# OCTA-STM.net
KiCad netlist of a schematic drawn in EAGLE
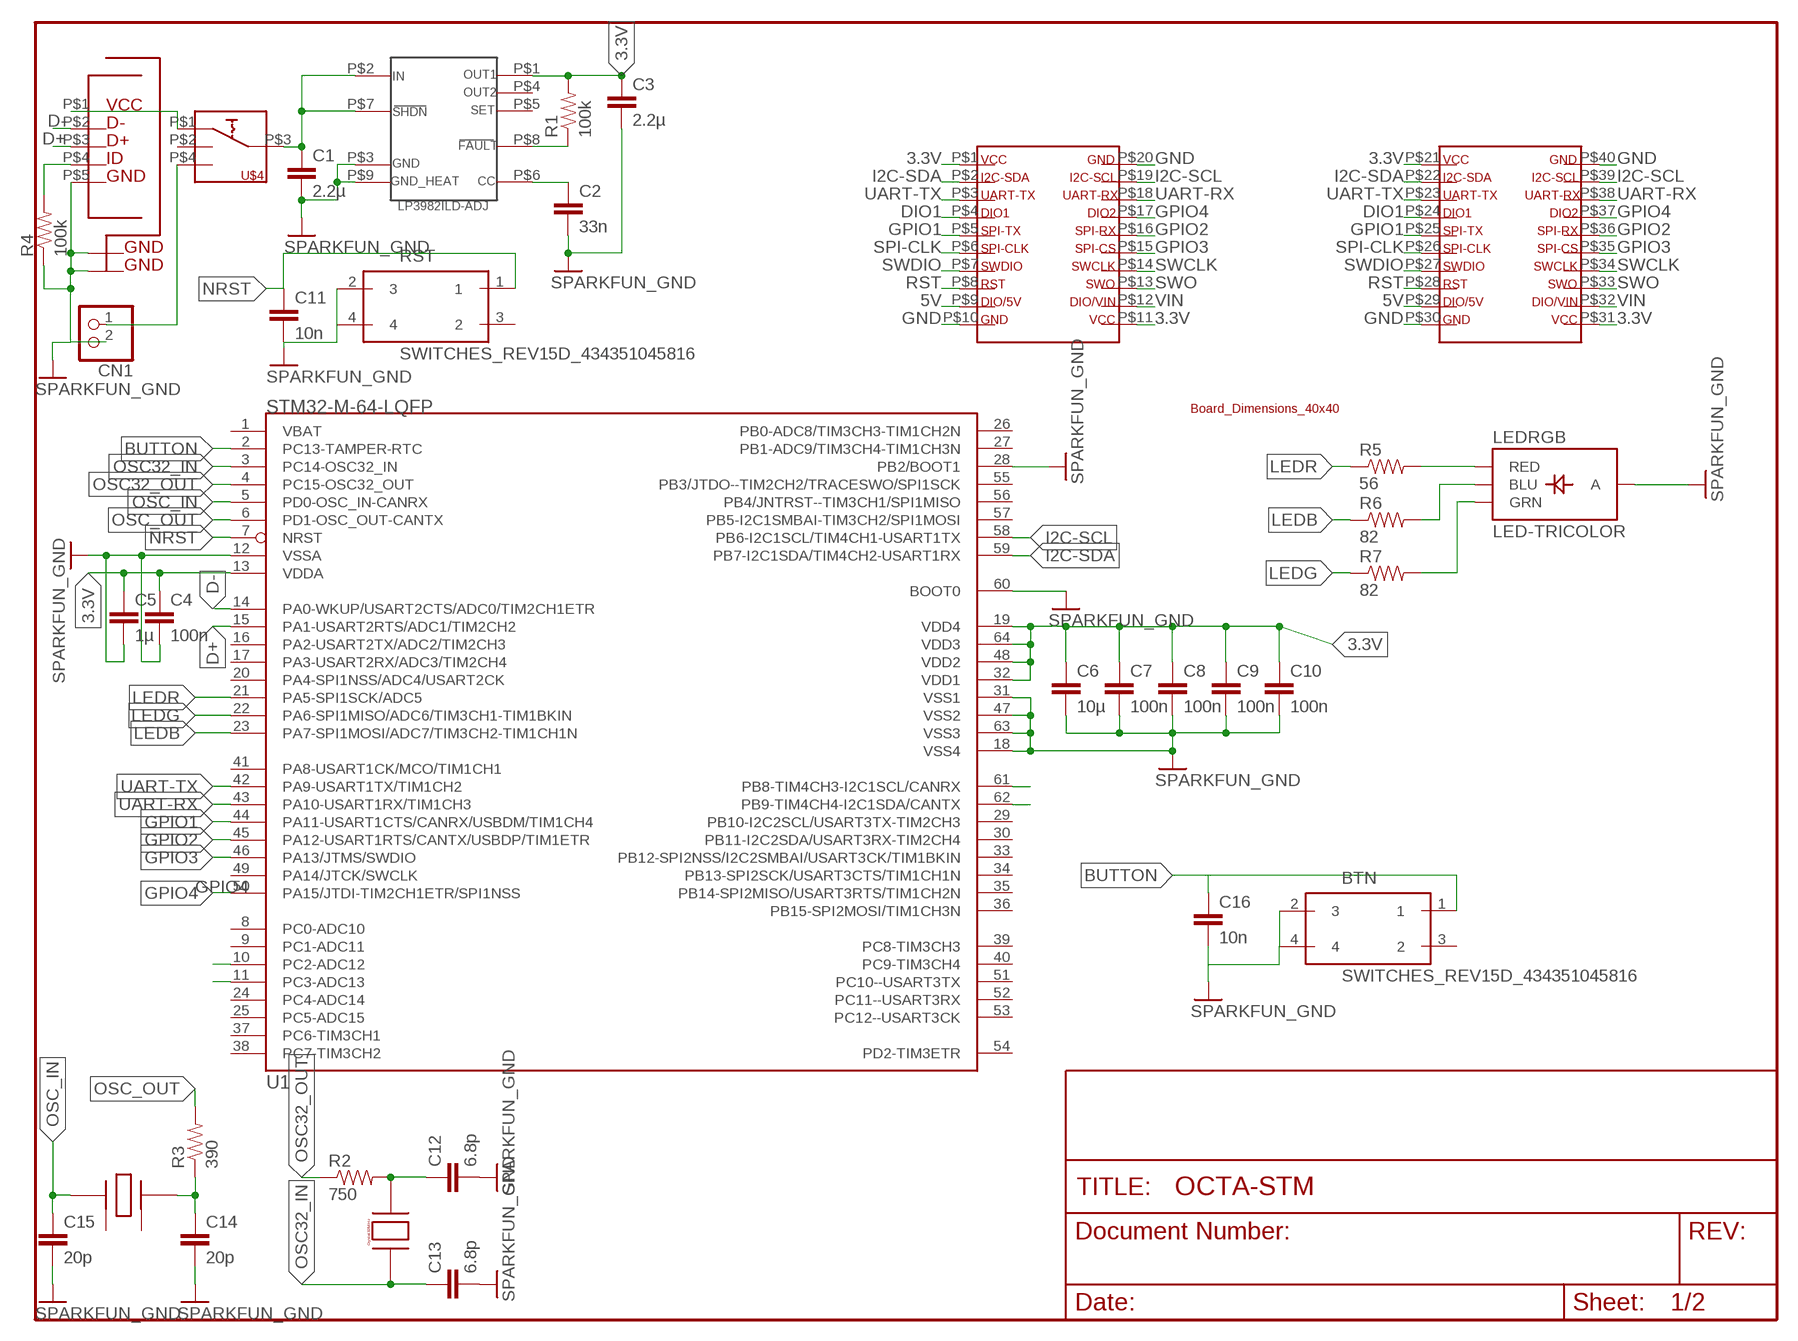
[diagram p0: schematic, sheet 1]
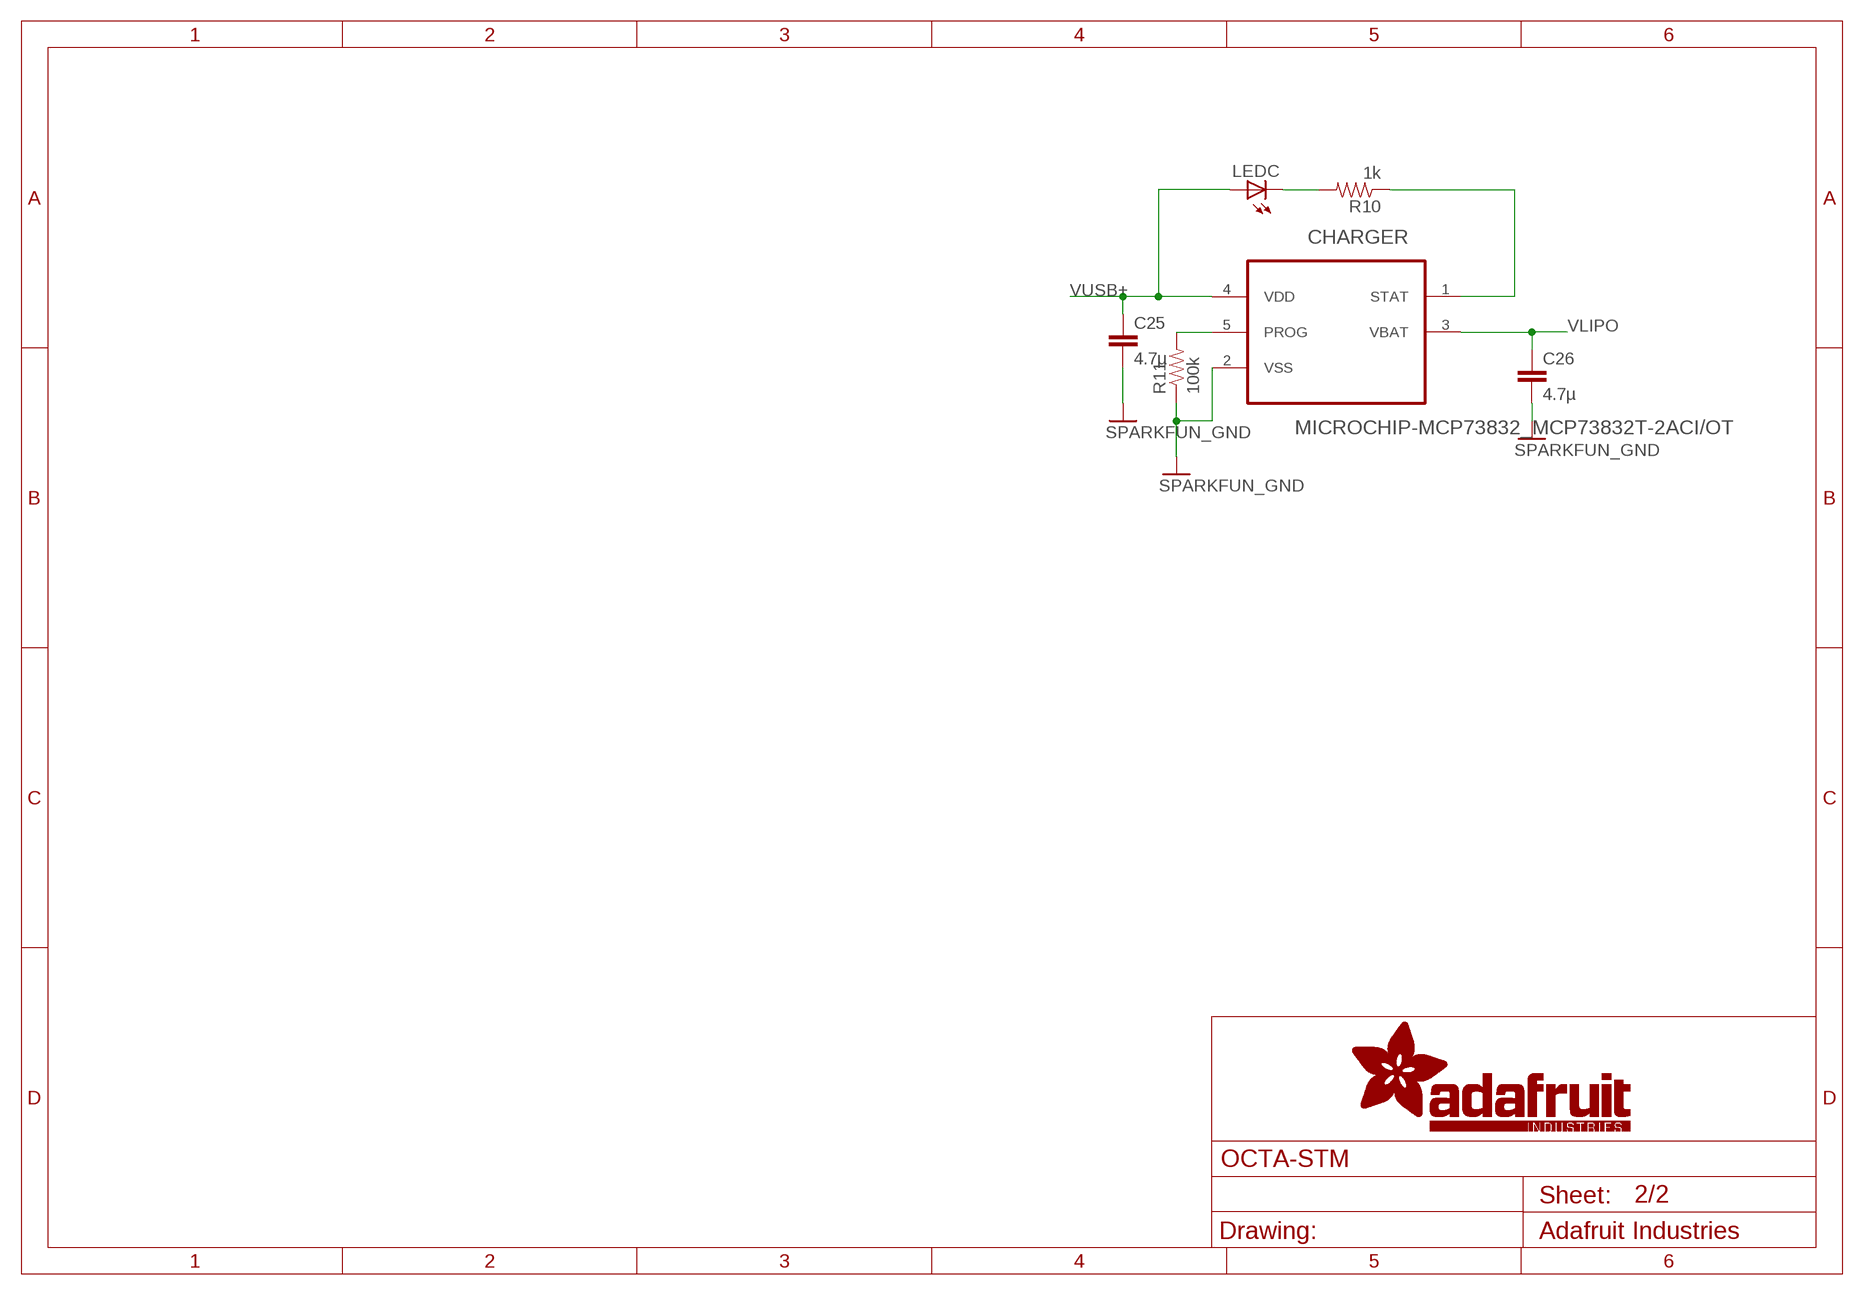
[diagram p1: schematic, sheet 2]

(export (version "E")
  (design (tool "Eeschema 10.0.6"))
  (components
    (comp (ref "BTN")
      (value "SWITCHES_REV15D_434351045816")
      (footprint "eagle-import:SWITCHES_REV15D_434351045816")
      (libsource (lib "eagle-import") (part "SWITCHES_REV15D_434351045816"))
    )
    (comp (ref "C1")
      (value "2.2µ")
      (footprint "eagle-import:SPARKFUN_0603-CAP")
      (libsource (lib "eagle-import") (part "SPARKFUN_CAP0603-CAP"))
    )
    (comp (ref "C2")
      (value "33n")
      (footprint "eagle-import:SPARKFUN_0603-CAP")
      (libsource (lib "eagle-import") (part "SPARKFUN_CAP0603-CAP"))
    )
    (comp (ref "C3")
      (value "2.2µ")
      (footprint "eagle-import:SPARKFUN_0603-CAP")
      (libsource (lib "eagle-import") (part "SPARKFUN_CAP0603-CAP"))
    )
    (comp (ref "C4")
      (value "100n")
      (footprint "eagle-import:SPARKFUN_0603-CAP")
      (libsource (lib "eagle-import") (part "SPARKFUN_CAP0603-CAP"))
    )
    (comp (ref "C5")
      (value "1µ")
      (footprint "eagle-import:SPARKFUN_0603-CAP")
      (libsource (lib "eagle-import") (part "SPARKFUN_CAP0603-CAP"))
    )
    (comp (ref "C6")
      (value "10µ")
      (footprint "eagle-import:SPARKFUN_0603-CAP")
      (libsource (lib "eagle-import") (part "SPARKFUN_CAP0603-CAP"))
    )
    (comp (ref "C7")
      (value "100n")
      (footprint "eagle-import:SPARKFUN_0603-CAP")
      (libsource (lib "eagle-import") (part "SPARKFUN_CAP0603-CAP"))
    )
    (comp (ref "C8")
      (value "100n")
      (footprint "eagle-import:SPARKFUN_0603-CAP")
      (libsource (lib "eagle-import") (part "SPARKFUN_CAP0603-CAP"))
    )
    (comp (ref "C9")
      (value "100n")
      (footprint "eagle-import:SPARKFUN_0603-CAP")
      (libsource (lib "eagle-import") (part "SPARKFUN_CAP0603-CAP"))
    )
    (comp (ref "C10")
      (value "100n")
      (footprint "eagle-import:SPARKFUN_0603-CAP")
      (libsource (lib "eagle-import") (part "SPARKFUN_CAP0603-CAP"))
    )
    (comp (ref "C11")
      (value "10n")
      (footprint "eagle-import:SPARKFUN_0603-CAP")
      (libsource (lib "eagle-import") (part "SPARKFUN_CAP0603-CAP"))
    )
    (comp (ref "C12")
      (value "6.8p")
      (footprint "eagle-import:SPARKFUN_0603-CAP")
      (libsource (lib "eagle-import") (part "SPARKFUN_CAP0603-CAP"))
    )
    (comp (ref "C13")
      (value "6.8p")
      (footprint "eagle-import:SPARKFUN_0603-CAP")
      (libsource (lib "eagle-import") (part "SPARKFUN_CAP0603-CAP"))
    )
    (comp (ref "C14")
      (value "20p")
      (footprint "eagle-import:SPARKFUN_0603-CAP")
      (libsource (lib "eagle-import") (part "SPARKFUN_CAP0603-CAP"))
    )
    (comp (ref "C15")
      (value "20p")
      (footprint "eagle-import:SPARKFUN_0603-CAP")
      (libsource (lib "eagle-import") (part "SPARKFUN_CAP0603-CAP"))
    )
    (comp (ref "C16")
      (value "10n")
      (footprint "eagle-import:SPARKFUN_0603-CAP")
      (libsource (lib "eagle-import") (part "SPARKFUN_CAP0603-CAP"))
    )
    (comp (ref "CN1")
      (value "ADAFRUIT_JST_2PIN-SMT-RA")
      (footprint "eagle-import:ADAFRUIT_JST-PH-2-SMT-RA")
      (libsource (lib "eagle-import") (part "ADAFRUIT_JST_2PIN-SMT-RA"))
    )
    (comp (ref "LEDRGB")
      (value "LED-TRICOLOR")
      (footprint "eagle-import:LED-TRICOLOR-SMD")
      (libsource (lib "eagle-import") (part "LED-TRICOLOR"))
    )
    (comp (ref "R1")
      (value "100k")
      (footprint "eagle-import:SPARKFUN_0603-RES")
      (libsource (lib "eagle-import") (part "SPARKFUN_RESISTOR0603-RES"))
    )
    (comp (ref "R2")
      (value "750")
      (footprint "eagle-import:SPARKFUN_0603-RES")
      (libsource (lib "eagle-import") (part "SPARKFUN_RESISTOR0603-RES"))
    )
    (comp (ref "R3")
      (value "390")
      (footprint "eagle-import:SPARKFUN_0603-RES")
      (libsource (lib "eagle-import") (part "SPARKFUN_RESISTOR0603-RES"))
    )
    (comp (ref "R4")
      (value "100k")
      (footprint "eagle-import:SPARKFUN_0603-RES")
      (libsource (lib "eagle-import") (part "SPARKFUN_RESISTOR0603-RES"))
    )
    (comp (ref "R5")
      (value "56")
      (footprint "eagle-import:SPARKFUN_0603-RES")
      (libsource (lib "eagle-import") (part "SPARKFUN_RESISTOR0603-RES"))
    )
    (comp (ref "R6")
      (value "82")
      (footprint "eagle-import:SPARKFUN_0603-RES")
      (libsource (lib "eagle-import") (part "SPARKFUN_RESISTOR0603-RES"))
    )
    (comp (ref "R7")
      (value "82")
      (footprint "eagle-import:SPARKFUN_0603-RES")
      (libsource (lib "eagle-import") (part "SPARKFUN_RESISTOR0603-RES"))
    )
    (comp (ref "RST")
      (value "SWITCHES_REV15D_434351045816")
      (footprint "eagle-import:SWITCHES_REV15D_434351045816")
      (libsource (lib "eagle-import") (part "SWITCHES_REV15D_434351045816"))
    )
    (comp (ref "U$1")
      (value "OCTA-CORE_MCIRO-USB2")
      (footprint "eagle-import:OCTA-CORE_MICRO-USB2")
      (libsource (lib "eagle-import") (part "OCTA-CORE_MCIRO-USB2"))
    )
    (comp (ref "U$2")
      (value "BOARD-DIMENSIONS-40X40")
      (footprint "eagle-import:BOARD-DIMENSIONS-40X40")
      (libsource (lib "eagle-import") (part "BOARD-DIMENSIONS-40X40"))
    )
    (comp (ref "U$3")
      (value "DRAGAN-PERSONAL_TI-3.3V-REGULATOR")
      (footprint "eagle-import:DRAGAN-PERSONAL_TI-3.3V-REGULATOR")
      (libsource (lib "eagle-import") (part "DRAGAN-PERSONAL_TI-3.3V-REGULATOR"))
    )
    (comp (ref "U$4")
      (value "OCTA-CORE_SP3T")
      (footprint "eagle-import:OCTA-CORE_SP3T")
      (libsource (lib "eagle-import") (part "OCTA-CORE_SP3T"))
    )
    (comp (ref "U$5")
      (value "DRAGAN-PERSONAL_CRYSTAL_32MHZ")
      (footprint "eagle-import:DRAGAN-PERSONAL_CRYSTAL_32MHZ")
      (libsource (lib "eagle-import") (part "DRAGAN-PERSONAL_CRYSTAL_32MHZ"))
    )
    (comp (ref "U$7")
      (value "DRAGAN-PERSONAL_XTAL-26MHZ")
      (footprint "eagle-import:DRAGAN-PERSONAL_XTAL-26MHZ")
      (libsource (lib "eagle-import") (part "DRAGAN-PERSONAL_XTAL-26MHZ"))
    )
    (comp (ref "U1")
      (value "STM32-M-64-LQFP")
      (footprint "eagle-import:LQFP64")
      (libsource (lib "eagle-import") (part "STM32-M-64-LQFP"))
    )
    (comp (ref "C25")
      (value "4.7µ")
      (footprint "eagle-import:SPARKFUN_0603-CAP")
      (libsource (lib "eagle-import") (part "SPARKFUN_CAP0603-CAP"))
    )
    (comp (ref "C26")
      (value "4.7µ")
      (footprint "eagle-import:SPARKFUN_0603-CAP")
      (libsource (lib "eagle-import") (part "SPARKFUN_CAP0603-CAP"))
    )
    (comp (ref "CHARGER")
      (value "MICROCHIP-MCP73832_MCP73832T-2ACI/OT")
      (footprint "eagle-import:MICROCHIP-MCP73832_SOT95P280X145-5N")
      (fields (field (name "MPN") "MCP73832T-2ACI/OT"))
      (libsource (lib "eagle-import") (part "MICROCHIP-MCP73832_MCP73832T-2ACI/OT"))
    )
    (comp (ref "LEDC")
      (value "LED_LEDCHIP-LED0805")
      (footprint "eagle-import:LED_CHIP-LED0805")
      (libsource (lib "eagle-import") (part "LED_LEDCHIP-LED0805"))
    )
    (comp (ref "R10")
      (value "1k")
      (footprint "eagle-import:SPARKFUN_0603-RES")
      (libsource (lib "eagle-import") (part "SPARKFUN_RESISTOR0603-RES"))
    )
    (comp (ref "R11")
      (value "100k")
      (footprint "eagle-import:SPARKFUN_0603-RES")
      (libsource (lib "eagle-import") (part "SPARKFUN_RESISTOR0603-RES"))
    )
  )
  (nets
    (net (code "1") (name "3.3V") (class "Default")
      (node (ref "C10") (pin "1") (pinfunction "1_1") (pintype "passive"))
      (node (ref "C3") (pin "1") (pinfunction "1_1") (pintype "passive"))
      (node (ref "C4") (pin "1") (pinfunction "1_1") (pintype "passive"))
      (node (ref "C5") (pin "1") (pinfunction "1_1") (pintype "passive"))
      (node (ref "C6") (pin "1") (pinfunction "1_1") (pintype "passive"))
      (node (ref "C7") (pin "1") (pinfunction "1_1") (pintype "passive"))
      (node (ref "C8") (pin "1") (pinfunction "1_1") (pintype "passive"))
      (node (ref "C9") (pin "1") (pinfunction "1_1") (pintype "passive"))
      (node (ref "R1") (pin "2") (pinfunction "2_2") (pintype "passive"))
      (node (ref "U$2") (pin "P$1") (pinfunction "P$1_P$1") (pintype "bidirectional"))
      (node (ref "U$2") (pin "P$11") (pinfunction "P$11_P$11") (pintype "bidirectional"))
      (node (ref "U$2") (pin "P$21") (pinfunction "P$21_P$21") (pintype "bidirectional"))
      (node (ref "U$2") (pin "P$31") (pinfunction "P$31_P$31") (pintype "bidirectional"))
      (node (ref "U$3") (pin "P$1") (pinfunction "P$1_P$1") (pintype "bidirectional"))
      (node (ref "U1") (pin "13") (pinfunction "VDDA_13") (pintype "power_in"))
      (node (ref "U1") (pin "19") (pinfunction "VDD4_19") (pintype "bidirectional"))
      (node (ref "U1") (pin "32") (pinfunction "VDD1_32") (pintype "power_in"))
      (node (ref "U1") (pin "48") (pinfunction "VDD2_48") (pintype "power_in"))
      (node (ref "U1") (pin "64") (pinfunction "VDD3_64") (pintype "power_in"))
    )
    (net (code "2") (name "5V") (class "Default")
      (node (ref "U$2") (pin "P$29") (pinfunction "P$29_P$29") (pintype "bidirectional"))
      (node (ref "U$2") (pin "P$9") (pinfunction "P$9_P$9") (pintype "bidirectional"))
    )
    (net (code "3") (name "BUTTON") (class "Default")
      (node (ref "BTN") (pin "1") (pinfunction "1_1") (pintype "bidirectional"))
      (node (ref "C16") (pin "1") (pinfunction "1_1") (pintype "passive"))
      (node (ref "U1") (pin "2") (pinfunction "PC13-TAMPER-RTC_2") (pintype "bidirectional"))
    )
    (net (code "4") (name "D+") (class "Default")
      (node (ref "U$1") (pin "P$3") (pinfunction "P$3_P$3") (pintype "bidirectional"))
      (node (ref "U1") (pin "15") (pinfunction "PA1-USART2RTS/ADC1/TIM2CH2_15") (pintype "bidirectional"))
    )
    (net (code "5") (name "D-") (class "Default")
      (node (ref "U$1") (pin "P$2") (pinfunction "P$2_P$2") (pintype "bidirectional"))
      (node (ref "U1") (pin "14") (pinfunction "PA0-WKUP/USART2CTS/ADC0/TIM2CH1ETR_14") (pintype "bidirectional"))
    )
    (net (code "6") (name "DIO1") (class "Default")
      (node (ref "U$2") (pin "P$24") (pinfunction "P$24_P$24") (pintype "bidirectional"))
      (node (ref "U$2") (pin "P$4") (pinfunction "P$4_P$4") (pintype "bidirectional"))
    )
    (net (code "7") (name "GND") (class "Default")
      (node (ref "BTN") (pin "2") (pinfunction "3_2") (pintype "bidirectional"))
      (node (ref "BTN") (pin "4") (pinfunction "4_4") (pintype "bidirectional"))
      (node (ref "C1") (pin "2") (pinfunction "2_2") (pintype "passive"))
      (node (ref "C10") (pin "2") (pinfunction "2_2") (pintype "passive"))
      (node (ref "C11") (pin "2") (pinfunction "2_2") (pintype "passive"))
      (node (ref "C12") (pin "2") (pinfunction "2_2") (pintype "passive"))
      (node (ref "C13") (pin "2") (pinfunction "2_2") (pintype "passive"))
      (node (ref "C14") (pin "2") (pinfunction "2_2") (pintype "passive"))
      (node (ref "C15") (pin "2") (pinfunction "2_2") (pintype "passive"))
      (node (ref "C16") (pin "2") (pinfunction "2_2") (pintype "passive"))
      (node (ref "C2") (pin "2") (pinfunction "2_2") (pintype "passive"))
      (node (ref "C25") (pin "2") (pinfunction "2_2") (pintype "passive"))
      (node (ref "C26") (pin "2") (pinfunction "2_2") (pintype "passive"))
      (node (ref "C3") (pin "2") (pinfunction "2_2") (pintype "passive"))
      (node (ref "C4") (pin "2") (pinfunction "2_2") (pintype "passive"))
      (node (ref "C5") (pin "2") (pinfunction "2_2") (pintype "passive"))
      (node (ref "C6") (pin "2") (pinfunction "2_2") (pintype "passive"))
      (node (ref "C7") (pin "2") (pinfunction "2_2") (pintype "passive"))
      (node (ref "C8") (pin "2") (pinfunction "2_2") (pintype "passive"))
      (node (ref "C9") (pin "2") (pinfunction "2_2") (pintype "passive"))
      (node (ref "CHARGER") (pin "2") (pinfunction "VSS_2") (pintype "power_in"))
      (node (ref "CN1") (pin "2") (pinfunction "1_2") (pintype "passive"))
      (node (ref "LEDRGB") (pin "A") (pinfunction "A_A") (pintype "bidirectional"))
      (node (ref "R11") (pin "1") (pinfunction "1_1") (pintype "passive"))
      (node (ref "R4") (pin "1") (pinfunction "1_1") (pintype "passive"))
      (node (ref "RST") (pin "2") (pinfunction "3_2") (pintype "bidirectional"))
      (node (ref "RST") (pin "4") (pinfunction "4_4") (pintype "bidirectional"))
      (node (ref "U$1") (pin "P$10") (pinfunction "P$7_P$10") (pintype "bidirectional"))
      (node (ref "U$1") (pin "P$11") (pinfunction "P$7_P$11") (pintype "bidirectional"))
      (node (ref "U$1") (pin "P$12") (pinfunction "P$6_P$12") (pintype "bidirectional"))
      (node (ref "U$1") (pin "P$13") (pinfunction "P$6_P$13") (pintype "bidirectional"))
      (node (ref "U$1") (pin "P$5") (pinfunction "P$5_P$5") (pintype "bidirectional"))
      (node (ref "U$1") (pin "P$6") (pinfunction "P$6_P$6") (pintype "bidirectional"))
      (node (ref "U$1") (pin "P$7") (pinfunction "P$6_P$7") (pintype "bidirectional"))
      (node (ref "U$1") (pin "P$8") (pinfunction "P$7_P$8") (pintype "bidirectional"))
      (node (ref "U$1") (pin "P$9") (pinfunction "P$7_P$9") (pintype "bidirectional"))
      (node (ref "U$2") (pin "P$10") (pinfunction "P$10_P$10") (pintype "bidirectional"))
      (node (ref "U$2") (pin "P$20") (pinfunction "P$20_P$20") (pintype "bidirectional"))
      (node (ref "U$2") (pin "P$30") (pinfunction "P$30_P$30") (pintype "bidirectional"))
      (node (ref "U$2") (pin "P$40") (pinfunction "P$40_P$40") (pintype "bidirectional"))
      (node (ref "U$3") (pin "P$3") (pinfunction "P$3_P$3") (pintype "bidirectional"))
      (node (ref "U$3") (pin "P$9") (pinfunction "P$9_P$9") (pintype "bidirectional"))
      (node (ref "U1") (pin "12") (pinfunction "VSSA_12") (pintype "power_in"))
      (node (ref "U1") (pin "18") (pinfunction "VSS4_18") (pintype "bidirectional"))
      (node (ref "U1") (pin "28") (pinfunction "PB2/BOOT1_28") (pintype "bidirectional"))
      (node (ref "U1") (pin "31") (pinfunction "VSS1_31") (pintype "power_in"))
      (node (ref "U1") (pin "47") (pinfunction "VSS2_47") (pintype "power_in"))
      (node (ref "U1") (pin "60") (pinfunction "BOOT0_60") (pintype "input"))
      (node (ref "U1") (pin "63") (pinfunction "VSS3_63") (pintype "power_in"))
    )
    (net (code "8") (name "GPIO1") (class "Default")
      (node (ref "U$2") (pin "P$25") (pinfunction "P$25_P$25") (pintype "bidirectional"))
      (node (ref "U$2") (pin "P$5") (pinfunction "P$5_P$5") (pintype "bidirectional"))
      (node (ref "U1") (pin "44") (pinfunction "PA11-USART1CTS/CANRX/USBDM/TIM1CH4_44") (pintype "bidirectional"))
    )
    (net (code "9") (name "GPIO2") (class "Default")
      (node (ref "U$2") (pin "P$16") (pinfunction "P$16_P$16") (pintype "bidirectional"))
      (node (ref "U$2") (pin "P$36") (pinfunction "P$36_P$36") (pintype "bidirectional"))
      (node (ref "U1") (pin "45") (pinfunction "PA12-USART1RTS/CANTX/USBDP/TIM1ETR_45") (pintype "bidirectional"))
    )
    (net (code "10") (name "GPIO3") (class "Default")
      (node (ref "U$2") (pin "P$15") (pinfunction "P$15_P$15") (pintype "bidirectional"))
      (node (ref "U$2") (pin "P$35") (pinfunction "P$35_P$35") (pintype "bidirectional"))
      (node (ref "U1") (pin "46") (pinfunction "PA13/JTMS/SWDIO_46") (pintype "bidirectional"))
    )
    (net (code "11") (name "GPIO4") (class "Default")
      (node (ref "U$2") (pin "P$17") (pinfunction "P$17_P$17") (pintype "bidirectional"))
      (node (ref "U$2") (pin "P$37") (pinfunction "P$37_P$37") (pintype "bidirectional"))
      (node (ref "U1") (pin "50") (pinfunction "PA15/JTDI-TIM2CH1ETR/SPI1NSS_50") (pintype "bidirectional"))
    )
    (net (code "12") (name "I2C-SCL") (class "Default")
      (node (ref "U$2") (pin "P$19") (pinfunction "P$19_P$19") (pintype "bidirectional"))
      (node (ref "U$2") (pin "P$39") (pinfunction "P$39_P$39") (pintype "bidirectional"))
      (node (ref "U1") (pin "58") (pinfunction "PB6-I2C1SCL/TIM4CH1-USART1TX_58") (pintype "bidirectional"))
    )
    (net (code "13") (name "I2C-SDA") (class "Default")
      (node (ref "U$2") (pin "P$2") (pinfunction "P$2_P$2") (pintype "bidirectional"))
      (node (ref "U$2") (pin "P$22") (pinfunction "P$22_P$22") (pintype "bidirectional"))
      (node (ref "U1") (pin "59") (pinfunction "PB7-I2C1SDA/TIM4CH2-USART1RX_59") (pintype "bidirectional"))
    )
    (net (code "14") (name "LEDB") (class "Default")
      (node (ref "R6") (pin "1") (pinfunction "1_1") (pintype "passive"))
      (node (ref "U1") (pin "23") (pinfunction "PA7-SPI1MOSI/ADC7/TIM3CH2-TIM1CH1N_23") (pintype "bidirectional"))
    )
    (net (code "15") (name "LEDG") (class "Default")
      (node (ref "R7") (pin "1") (pinfunction "1_1") (pintype "passive"))
      (node (ref "U1") (pin "22") (pinfunction "PA6-SPI1MISO/ADC6/TIM3CH1-TIM1BKIN_22") (pintype "bidirectional"))
    )
    (net (code "16") (name "LEDR") (class "Default")
      (node (ref "R5") (pin "1") (pinfunction "1_1") (pintype "passive"))
      (node (ref "U1") (pin "21") (pinfunction "PA5-SPI1SCK/ADC5_21") (pintype "bidirectional"))
    )
    (net (code "17") (name "NRST") (class "Default")
      (node (ref "C11") (pin "1") (pinfunction "1_1") (pintype "passive"))
      (node (ref "RST") (pin "1") (pinfunction "1_1") (pintype "bidirectional"))
      (node (ref "U1") (pin "7") (pinfunction "NRST_7") (pintype "bidirectional"))
    )
    (net (code "18") (name "Net-(C1-Pad1)") (class "Default")
      (node (ref "C1") (pin "1") (pinfunction "1_1") (pintype "passive"))
      (node (ref "U$3") (pin "P$2") (pinfunction "P$2_P$2") (pintype "bidirectional"))
      (node (ref "U$3") (pin "P$7") (pinfunction "P$7_P$7") (pintype "bidirectional"))
      (node (ref "U$4") (pin "P$3") (pinfunction "P$3_P$3") (pintype "bidirectional"))
    )
    (net (code "19") (name "Net-(C2-Pad1)") (class "Default")
      (node (ref "C2") (pin "1") (pinfunction "1_1") (pintype "passive"))
      (node (ref "U$3") (pin "P$6") (pinfunction "P$6_P$6") (pintype "bidirectional"))
    )
    (net (code "20") (name "Net-(C14-Pad1)") (class "Default")
      (node (ref "C14") (pin "1") (pinfunction "1_1") (pintype "passive"))
      (node (ref "R3") (pin "1") (pinfunction "1_1") (pintype "passive"))
      (node (ref "U$7") (pin "P$3") (pinfunction "P$3_P$3") (pintype "bidirectional"))
    )
    (net (code "21") (name "Net-(CHARGER-PROG)") (class "Default")
      (node (ref "CHARGER") (pin "5") (pinfunction "PROG_5") (pintype "input"))
      (node (ref "R11") (pin "2") (pinfunction "2_2") (pintype "passive"))
    )
    (net (code "22") (name "Net-(CHARGER-STAT)") (class "Default")
      (node (ref "CHARGER") (pin "1") (pinfunction "STAT_1") (pintype "output"))
      (node (ref "R10") (pin "1") (pinfunction "1_1") (pintype "passive"))
    )
    (net (code "23") (name "Net-(LEDC-PadC)") (class "Default")
      (node (ref "LEDC") (pin "C") (pinfunction "C_C") (pintype "passive"))
      (node (ref "R10") (pin "2") (pinfunction "2_2") (pintype "passive"))
    )
    (net (code "24") (name "Net-(LEDRGB-BLU)") (class "Default")
      (node (ref "LEDRGB") (pin "B") (pinfunction "BLU_B") (pintype "bidirectional"))
      (node (ref "R6") (pin "2") (pinfunction "2_2") (pintype "passive"))
    )
    (net (code "25") (name "Net-(LEDRGB-GRN)") (class "Default")
      (node (ref "LEDRGB") (pin "G") (pinfunction "GRN_G") (pintype "bidirectional"))
      (node (ref "R7") (pin "2") (pinfunction "2_2") (pintype "passive"))
    )
    (net (code "26") (name "Net-(LEDRGB-RED)") (class "Default")
      (node (ref "LEDRGB") (pin "R") (pinfunction "RED_R") (pintype "bidirectional"))
      (node (ref "R5") (pin "2") (pinfunction "2_2") (pintype "passive"))
    )
    (net (code "27") (name "Net-(R1-Pad1)") (class "Default")
      (node (ref "R1") (pin "1") (pinfunction "1_1") (pintype "passive"))
      (node (ref "U$3") (pin "P$8") (pinfunction "P$8_P$8") (pintype "bidirectional"))
    )
    (net (code "28") (name "Net-(R4-Pad2)") (class "Default")
      (node (ref "R4") (pin "2") (pinfunction "2_2") (pintype "passive"))
      (node (ref "U$1") (pin "P$4") (pinfunction "P$4_P$4") (pintype "bidirectional"))
    )
    (net (code "29") (name "Net-(U$5-P$1)") (class "Default")
      (node (ref "C12") (pin "1") (pinfunction "1_1") (pintype "passive"))
      (node (ref "R2") (pin "2") (pinfunction "2_2") (pintype "passive"))
      (node (ref "U$5") (pin "P$2") (pinfunction "P$1_P$2") (pintype "bidirectional"))
    )
    (net (code "30") (name "OSC32_IN") (class "Default")
      (node (ref "C13") (pin "1") (pinfunction "1_1") (pintype "passive"))
      (node (ref "U$5") (pin "P$3") (pinfunction "P$2_P$3") (pintype "bidirectional"))
      (node (ref "U1") (pin "3") (pinfunction "PC14-OSC32_IN_3") (pintype "bidirectional"))
    )
    (net (code "31") (name "OSC32_OUT") (class "Default")
      (node (ref "R2") (pin "1") (pinfunction "1_1") (pintype "passive"))
      (node (ref "U1") (pin "4") (pinfunction "PC15-OSC32_OUT_4") (pintype "bidirectional"))
    )
    (net (code "32") (name "OSC_IN") (class "Default")
      (node (ref "C15") (pin "1") (pinfunction "1_1") (pintype "passive"))
      (node (ref "U$7") (pin "P$1") (pinfunction "P$1_P$1") (pintype "bidirectional"))
      (node (ref "U1") (pin "5") (pinfunction "PD0-OSC_IN-CANRX_5") (pintype "input"))
    )
    (net (code "33") (name "OSC_OUT") (class "Default")
      (node (ref "R3") (pin "2") (pinfunction "2_2") (pintype "passive"))
      (node (ref "U1") (pin "6") (pinfunction "PD1-OSC_OUT-CANTX_6") (pintype "output"))
    )
    (net (code "34") (name "RST") (class "Default")
      (node (ref "U$2") (pin "P$28") (pinfunction "P$28_P$28") (pintype "bidirectional"))
      (node (ref "U$2") (pin "P$8") (pinfunction "P$8_P$8") (pintype "bidirectional"))
    )
    (net (code "35") (name "SPI-CLK") (class "Default")
      (node (ref "U$2") (pin "P$26") (pinfunction "P$26_P$26") (pintype "bidirectional"))
      (node (ref "U$2") (pin "P$6") (pinfunction "P$6_P$6") (pintype "bidirectional"))
    )
    (net (code "36") (name "SWCLK") (class "Default")
      (node (ref "U$2") (pin "P$14") (pinfunction "P$14_P$14") (pintype "bidirectional"))
      (node (ref "U$2") (pin "P$34") (pinfunction "P$34_P$34") (pintype "bidirectional"))
    )
    (net (code "37") (name "SWDIO") (class "Default")
      (node (ref "U$2") (pin "P$27") (pinfunction "P$27_P$27") (pintype "bidirectional"))
      (node (ref "U$2") (pin "P$7") (pinfunction "P$7_P$7") (pintype "bidirectional"))
    )
    (net (code "38") (name "SWO") (class "Default")
      (node (ref "U$2") (pin "P$13") (pinfunction "P$13_P$13") (pintype "bidirectional"))
      (node (ref "U$2") (pin "P$33") (pinfunction "P$33_P$33") (pintype "bidirectional"))
    )
    (net (code "39") (name "UART-RX") (class "Default")
      (node (ref "U$2") (pin "P$18") (pinfunction "P$18_P$18") (pintype "bidirectional"))
      (node (ref "U$2") (pin "P$38") (pinfunction "P$38_P$38") (pintype "bidirectional"))
      (node (ref "U1") (pin "43") (pinfunction "PA10-USART1RX/TIM1CH3_43") (pintype "bidirectional"))
    )
    (net (code "40") (name "UART-TX") (class "Default")
      (node (ref "U$2") (pin "P$23") (pinfunction "P$23_P$23") (pintype "bidirectional"))
      (node (ref "U$2") (pin "P$3") (pinfunction "P$3_P$3") (pintype "bidirectional"))
      (node (ref "U1") (pin "42") (pinfunction "PA9-USART1TX/TIM1CH2_42") (pintype "bidirectional"))
    )
    (net (code "41") (name "VBAT") (class "Default")
      (node (ref "U1") (pin "1") (pinfunction "VBAT_1") (pintype "power_in"))
    )
    (net (code "42") (name "VIN") (class "Default")
      (node (ref "U$2") (pin "P$12") (pinfunction "P$12_P$12") (pintype "bidirectional"))
      (node (ref "U$2") (pin "P$32") (pinfunction "P$32_P$32") (pintype "bidirectional"))
    )
    (net (code "43") (name "VLIPO") (class "Default")
      (node (ref "C26") (pin "1") (pinfunction "1_1") (pintype "passive"))
      (node (ref "CHARGER") (pin "3") (pinfunction "VBAT_3") (pintype "output"))
      (node (ref "CN1") (pin "1") (pinfunction "2_1") (pintype "passive"))
      (node (ref "U$4") (pin "P$4") (pinfunction "P$4_P$4") (pintype "bidirectional"))
    )
    (net (code "44") (name "VUSB+") (class "Default")
      (node (ref "C25") (pin "1") (pinfunction "1_1") (pintype "passive"))
      (node (ref "CHARGER") (pin "4") (pinfunction "VDD_4") (pintype "power_in"))
      (node (ref "LEDC") (pin "A") (pinfunction "A_A") (pintype "passive"))
      (node (ref "U$1") (pin "P$1") (pinfunction "P$1_P$1") (pintype "bidirectional"))
      (node (ref "U$4") (pin "P$1") (pinfunction "P$1_P$1") (pintype "bidirectional"))
    )
    (net (code "45") (name "unconnected-(BTN-2-Pad3)") (class "Default")
      (node (ref "BTN") (pin "3") (pinfunction "2_3") (pintype "bidirectional"))
    )
    (net (code "46") (name "unconnected-(RST-2-Pad3)") (class "Default")
      (node (ref "RST") (pin "3") (pinfunction "2_3") (pintype "bidirectional"))
    )
    (net (code "47") (name "unconnected-(U$3-PadP$4)") (class "Default")
      (node (ref "U$3") (pin "P$4") (pinfunction "P$4_P$4") (pintype "bidirectional"))
    )
    (net (code "48") (name "unconnected-(U$3-PadP$5)") (class "Default")
      (node (ref "U$3") (pin "P$5") (pinfunction "P$5_P$5") (pintype "bidirectional"))
    )
    (net (code "49") (name "unconnected-(U$4-PadP$2)") (class "Default")
      (node (ref "U$4") (pin "P$2") (pinfunction "P$2_P$2") (pintype "bidirectional"))
    )
    (net (code "50") (name "unconnected-(U$7-PadP$2)") (class "Default")
      (node (ref "U$7") (pin "P$2") (pinfunction "P$2_P$2") (pintype "bidirectional"))
    )
    (net (code "51") (name "unconnected-(U$7-PadP$4)") (class "Default")
      (node (ref "U$7") (pin "P$4") (pinfunction "P$4_P$4") (pintype "bidirectional"))
    )
    (net (code "52") (name "unconnected-(U1-PA2-USART2TX{slash}ADC2{slash}TIM2CH3-Pad16)") (class "Default")
      (node (ref "U1") (pin "16") (pinfunction "PA2-USART2TX/ADC2/TIM2CH3_16") (pintype "bidirectional"))
    )
    (net (code "53") (name "unconnected-(U1-PA3-USART2RX{slash}ADC3{slash}TIM2CH4-Pad17)") (class "Default")
      (node (ref "U1") (pin "17") (pinfunction "PA3-USART2RX/ADC3/TIM2CH4_17") (pintype "bidirectional"))
    )
    (net (code "54") (name "unconnected-(U1-PA4-SPI1NSS{slash}ADC4{slash}USART2CK-Pad20)") (class "Default")
      (node (ref "U1") (pin "20") (pinfunction "PA4-SPI1NSS/ADC4/USART2CK_20") (pintype "bidirectional"))
    )
    (net (code "55") (name "unconnected-(U1-PA8-USART1CK{slash}MCO{slash}TIM1CH1-Pad41)") (class "Default")
      (node (ref "U1") (pin "41") (pinfunction "PA8-USART1CK/MCO/TIM1CH1_41") (pintype "bidirectional"))
    )
    (net (code "56") (name "unconnected-(U1-PA14{slash}JTCK{slash}SWCLK-Pad49)") (class "Default")
      (node (ref "U1") (pin "49") (pinfunction "PA14/JTCK/SWCLK_49") (pintype "bidirectional"))
    )
    (net (code "57") (name "unconnected-(U1-PB0-ADC8{slash}TIM3CH3-TIM1CH2N-Pad26)") (class "Default")
      (node (ref "U1") (pin "26") (pinfunction "PB0-ADC8/TIM3CH3-TIM1CH2N_26") (pintype "bidirectional"))
    )
    (net (code "58") (name "unconnected-(U1-PB1-ADC9{slash}TIM3CH4-TIM1CH3N-Pad27)") (class "Default")
      (node (ref "U1") (pin "27") (pinfunction "PB1-ADC9/TIM3CH4-TIM1CH3N_27") (pintype "bidirectional"))
    )
    (net (code "59") (name "unconnected-(U1-PB3{slash}JTDO--TIM2CH2{slash}TRACESWO{slash}SPI1SCK-Pad55)") (class "Default")
      (node (ref "U1") (pin "55") (pinfunction "PB3/JTDO--TIM2CH2/TRACESWO/SPI1SCK_55") (pintype "bidirectional"))
    )
    (net (code "60") (name "unconnected-(U1-PB4{slash}JNTRST--TIM3CH1{slash}SPI1MISO-Pad56)") (class "Default")
      (node (ref "U1") (pin "56") (pinfunction "PB4/JNTRST--TIM3CH1/SPI1MISO_56") (pintype "bidirectional"))
    )
    (net (code "61") (name "unconnected-(U1-PB5-I2C1SMBAI-TIM3CH2{slash}SPI1MOSI-Pad57)") (class "Default")
      (node (ref "U1") (pin "57") (pinfunction "PB5-I2C1SMBAI-TIM3CH2/SPI1MOSI_57") (pintype "bidirectional"))
    )
    (net (code "62") (name "unconnected-(U1-PB8-TIM4CH3-I2C1SCL{slash}CANRX-Pad61)") (class "Default")
      (node (ref "U1") (pin "61") (pinfunction "PB8-TIM4CH3-I2C1SCL/CANRX_61") (pintype "bidirectional"))
    )
    (net (code "63") (name "unconnected-(U1-PB9-TIM4CH4-I2C1SDA{slash}CANTX-Pad62)") (class "Default")
      (node (ref "U1") (pin "62") (pinfunction "PB9-TIM4CH4-I2C1SDA/CANTX_62") (pintype "bidirectional"))
    )
    (net (code "64") (name "unconnected-(U1-PB10-I2C2SCL{slash}USART3TX-TIM2CH3-Pad29)") (class "Default")
      (node (ref "U1") (pin "29") (pinfunction "PB10-I2C2SCL/USART3TX-TIM2CH3_29") (pintype "bidirectional"))
    )
    (net (code "65") (name "unconnected-(U1-PB11-I2C2SDA{slash}USART3RX-TIM2CH4-Pad30)") (class "Default")
      (node (ref "U1") (pin "30") (pinfunction "PB11-I2C2SDA/USART3RX-TIM2CH4_30") (pintype "bidirectional"))
    )
    (net (code "66") (name "unconnected-(U1-PB12-SPI2NSS{slash}I2C2SMBAI{slash}USART3CK{slash}TIM1BKIN-Pad33)") (class "Default")
      (node (ref "U1") (pin "33") (pinfunction "PB12-SPI2NSS/I2C2SMBAI/USART3CK/TIM1BKIN_33") (pintype "bidirectional"))
    )
    (net (code "67") (name "unconnected-(U1-PB13-SPI2SCK{slash}USART3CTS{slash}TIM1CH1N-Pad34)") (class "Default")
      (node (ref "U1") (pin "34") (pinfunction "PB13-SPI2SCK/USART3CTS/TIM1CH1N_34") (pintype "bidirectional"))
    )
    (net (code "68") (name "unconnected-(U1-PB14-SPI2MISO{slash}USART3RTS{slash}TIM1CH2N-Pad35)") (class "Default")
      (node (ref "U1") (pin "35") (pinfunction "PB14-SPI2MISO/USART3RTS/TIM1CH2N_35") (pintype "bidirectional"))
    )
    (net (code "69") (name "unconnected-(U1-PB15-SPI2MOSI{slash}TIM1CH3N-Pad36)") (class "Default")
      (node (ref "U1") (pin "36") (pinfunction "PB15-SPI2MOSI/TIM1CH3N_36") (pintype "bidirectional"))
    )
    (net (code "70") (name "unconnected-(U1-PC0-ADC10-Pad8)") (class "Default")
      (node (ref "U1") (pin "8") (pinfunction "PC0-ADC10_8") (pintype "bidirectional"))
    )
    (net (code "71") (name "unconnected-(U1-PC1-ADC11-Pad9)") (class "Default")
      (node (ref "U1") (pin "9") (pinfunction "PC1-ADC11_9") (pintype "bidirectional"))
    )
    (net (code "72") (name "unconnected-(U1-PC2-ADC12-Pad10)") (class "Default")
      (node (ref "U1") (pin "10") (pinfunction "PC2-ADC12_10") (pintype "bidirectional"))
    )
    (net (code "73") (name "unconnected-(U1-PC3-ADC13-Pad11)") (class "Default")
      (node (ref "U1") (pin "11") (pinfunction "PC3-ADC13_11") (pintype "bidirectional"))
    )
    (net (code "74") (name "unconnected-(U1-PC4-ADC14-Pad24)") (class "Default")
      (node (ref "U1") (pin "24") (pinfunction "PC4-ADC14_24") (pintype "bidirectional"))
    )
    (net (code "75") (name "unconnected-(U1-PC5-ADC15-Pad25)") (class "Default")
      (node (ref "U1") (pin "25") (pinfunction "PC5-ADC15_25") (pintype "bidirectional"))
    )
    (net (code "76") (name "unconnected-(U1-PC6-TIM3CH1-Pad37)") (class "Default")
      (node (ref "U1") (pin "37") (pinfunction "PC6-TIM3CH1_37") (pintype "bidirectional"))
    )
    (net (code "77") (name "unconnected-(U1-PC7-TIM3CH2-Pad38)") (class "Default")
      (node (ref "U1") (pin "38") (pinfunction "PC7-TIM3CH2_38") (pintype "bidirectional"))
    )
    (net (code "78") (name "unconnected-(U1-PC8-TIM3CH3-Pad39)") (class "Default")
      (node (ref "U1") (pin "39") (pinfunction "PC8-TIM3CH3_39") (pintype "bidirectional"))
    )
    (net (code "79") (name "unconnected-(U1-PC9-TIM3CH4-Pad40)") (class "Default")
      (node (ref "U1") (pin "40") (pinfunction "PC9-TIM3CH4_40") (pintype "bidirectional"))
    )
    (net (code "80") (name "unconnected-(U1-PC10--USART3TX-Pad51)") (class "Default")
      (node (ref "U1") (pin "51") (pinfunction "PC10--USART3TX_51") (pintype "bidirectional"))
    )
    (net (code "81") (name "unconnected-(U1-PC11--USART3RX-Pad52)") (class "Default")
      (node (ref "U1") (pin "52") (pinfunction "PC11--USART3RX_52") (pintype "bidirectional"))
    )
    (net (code "82") (name "unconnected-(U1-PC12--USART3CK-Pad53)") (class "Default")
      (node (ref "U1") (pin "53") (pinfunction "PC12--USART3CK_53") (pintype "bidirectional"))
    )
    (net (code "83") (name "unconnected-(U1-PD2-TIM3ETR-Pad54)") (class "Default")
      (node (ref "U1") (pin "54") (pinfunction "PD2-TIM3ETR_54") (pintype "bidirectional"))
    )
  )
)
